# SD_Sniffer.net
KiCad netlist of a schematic drawn in EAGLE
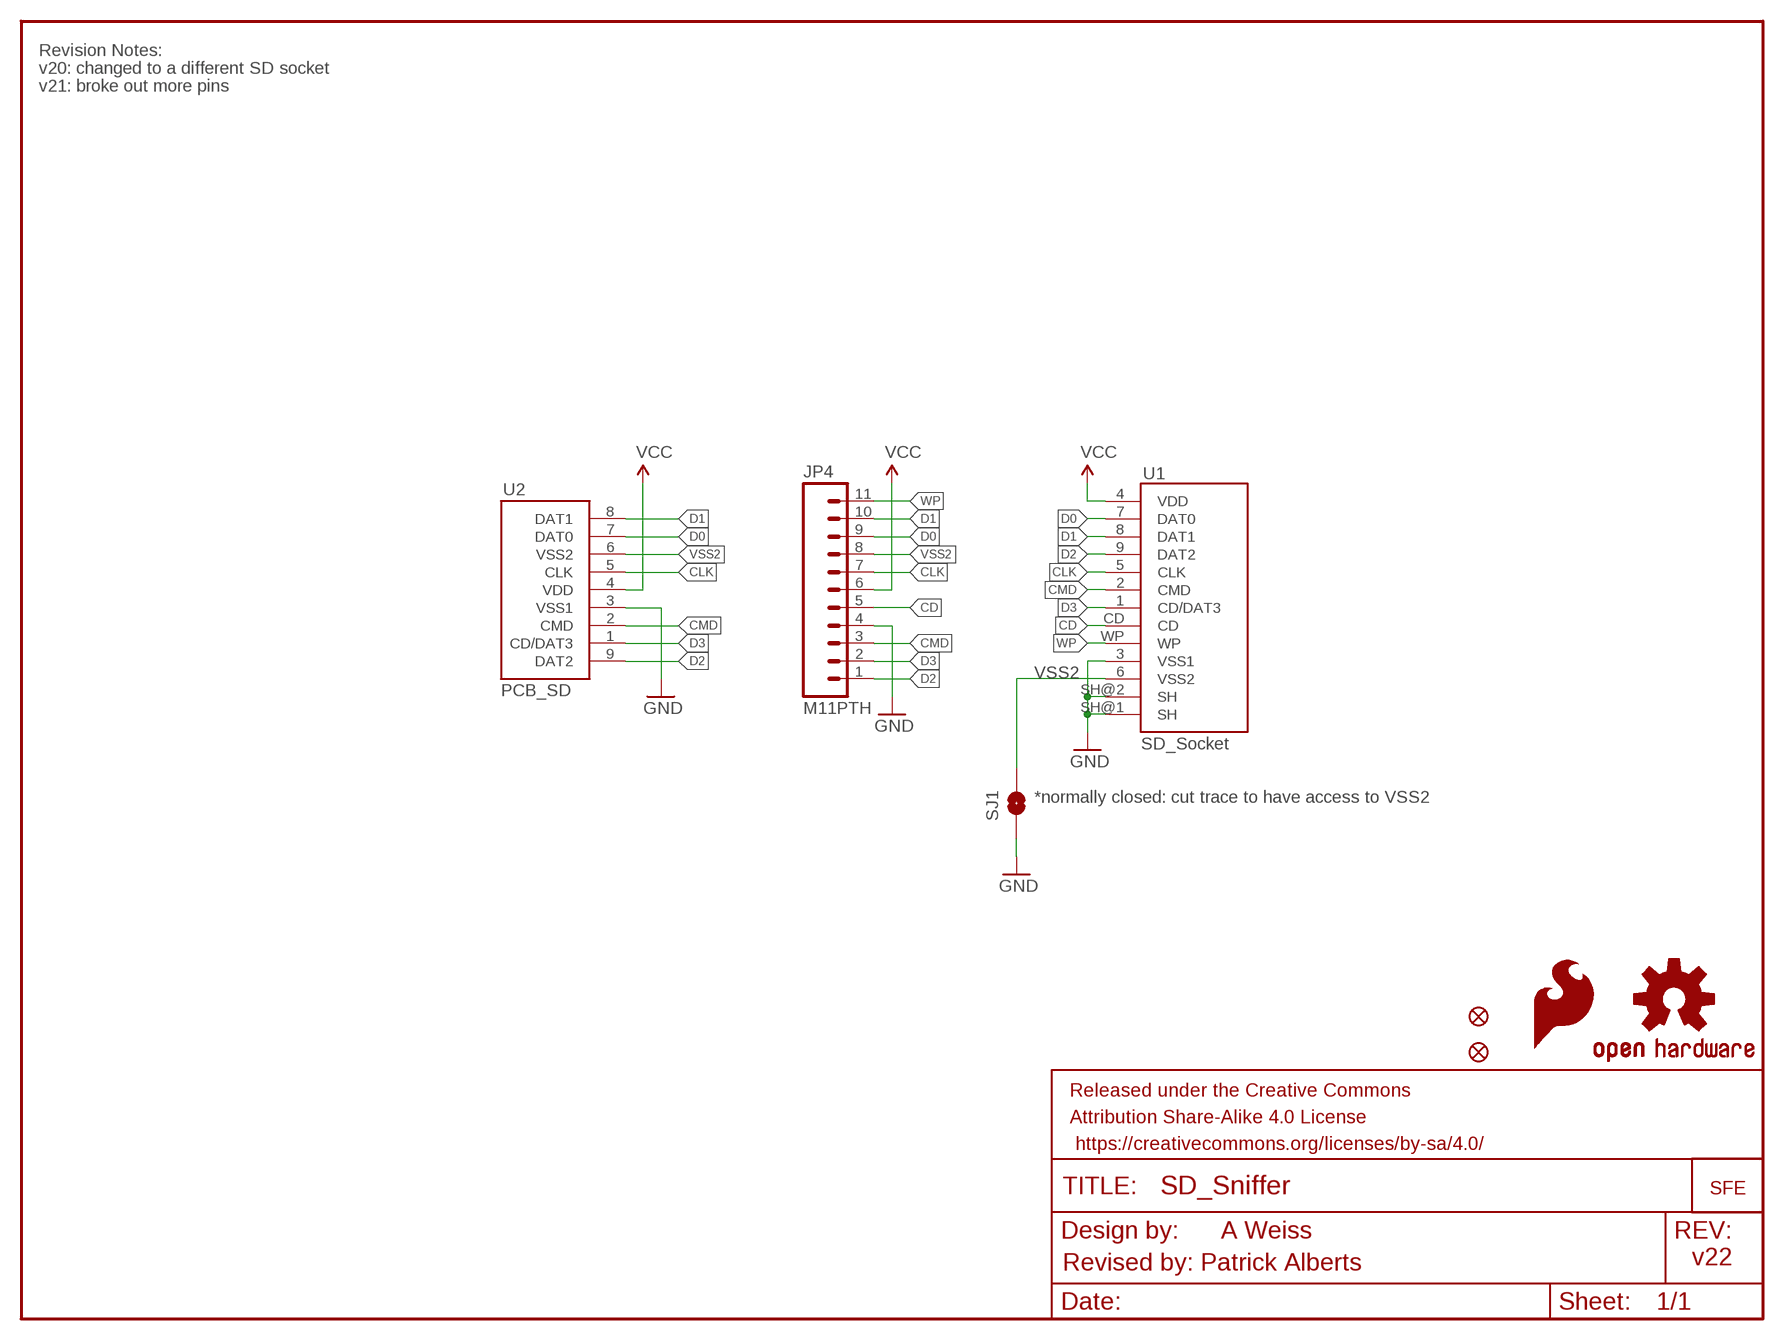
[diagram p0: schematic, sheet 1]

(export (version "E")
  (design (tool "Eeschema 10.0.6"))
  (components
    (comp (ref "FRAME1")
      (value "FRAME-LETTER")
      (footprint "eagle-import:CREATIVE_COMMONS")
      (libsource (lib "eagle-import") (part "FRAME-LETTER"))
    )
    (comp (ref "JP2")
      (value "FIDUCIALUFIDUCIAL")
      (footprint "eagle-import:MICRO-FIDUCIAL")
      (libsource (lib "eagle-import") (part "FIDUCIALUFIDUCIAL"))
    )
    (comp (ref "JP3")
      (value "FIDUCIALUFIDUCIAL")
      (footprint "eagle-import:MICRO-FIDUCIAL")
      (libsource (lib "eagle-import") (part "FIDUCIALUFIDUCIAL"))
    )
    (comp (ref "JP4")
      (value "M11PTH")
      (footprint "eagle-import:1X11")
      (libsource (lib "eagle-import") (part "M11PTH"))
    )
    (comp (ref "LOGO")
      (value "LOGO-SFENEW")
      (footprint "eagle-import:SFE-NEW-WEBLOGO")
      (libsource (lib "eagle-import") (part "LOGO-SFENEW"))
    )
    (comp (ref "SJ1")
      (value "SOLDERJUMPERTRACE")
      (footprint "eagle-import:SJ_2S-TRACE")
      (libsource (lib "eagle-import") (part "SOLDERJUMPERTRACE"))
    )
    (comp (ref "U$2")
      (value "OSHW-LOGOS")
      (footprint "eagle-import:OSHW-LOGO-S")
      (libsource (lib "eagle-import") (part "OSHW-LOGOS"))
    )
    (comp (ref "U$4")
      (value "SFE_LOGO_FLAME.2_INCH")
      (footprint "eagle-import:SFE_LOGO_FLAME_.2")
      (libsource (lib "eagle-import") (part "SFE_LOGO_FLAME.2_INCH"))
    )
    (comp (ref "U1")
      (value "SD_CARD_SOCKET")
      (footprint "eagle-import:SD_1_1")
      (libsource (lib "eagle-import") (part "SD_CARD_SOCKET"))
    )
    (comp (ref "U2")
      (value "SD_MMC_CARDSD_PCB")
      (footprint "eagle-import:SD-MMC-CARD")
      (libsource (lib "eagle-import") (part "SD_MMC_CARDSD_PCB"))
    )
  )
  (nets
    (net (code "1") (name "CD") (class "Default")
      (node (ref "JP4") (pin "5") (pinfunction "5_5") (pintype "passive"))
      (node (ref "U1") (pin "CD") (pinfunction "CD_CD") (pintype "bidirectional"))
    )
    (net (code "2") (name "CLK") (class "Default")
      (node (ref "JP4") (pin "7") (pinfunction "7_7") (pintype "passive"))
      (node (ref "U1") (pin "5") (pinfunction "CLK_5") (pintype "bidirectional"))
      (node (ref "U2") (pin "5") (pinfunction "CLK_5") (pintype "bidirectional"))
    )
    (net (code "3") (name "CMD") (class "Default")
      (node (ref "JP4") (pin "3") (pinfunction "3_3") (pintype "passive"))
      (node (ref "U1") (pin "2") (pinfunction "CMD_2") (pintype "bidirectional"))
      (node (ref "U2") (pin "2") (pinfunction "CMD_2") (pintype "bidirectional"))
    )
    (net (code "4") (name "D0") (class "Default")
      (node (ref "JP4") (pin "9") (pinfunction "9_9") (pintype "passive"))
      (node (ref "U1") (pin "7") (pinfunction "DAT0_7") (pintype "bidirectional"))
      (node (ref "U2") (pin "7") (pinfunction "DAT0_7") (pintype "bidirectional"))
    )
    (net (code "5") (name "D1") (class "Default")
      (node (ref "JP4") (pin "10") (pinfunction "10_10") (pintype "passive"))
      (node (ref "U1") (pin "8") (pinfunction "DAT1_8") (pintype "bidirectional"))
      (node (ref "U2") (pin "8") (pinfunction "DAT1_8") (pintype "bidirectional"))
    )
    (net (code "6") (name "D2") (class "Default")
      (node (ref "JP4") (pin "1") (pinfunction "1_1") (pintype "passive"))
      (node (ref "U1") (pin "9") (pinfunction "DAT2_9") (pintype "bidirectional"))
      (node (ref "U2") (pin "9") (pinfunction "DAT2_9") (pintype "bidirectional"))
    )
    (net (code "7") (name "D3") (class "Default")
      (node (ref "JP4") (pin "2") (pinfunction "2_2") (pintype "passive"))
      (node (ref "U1") (pin "1") (pinfunction "CD/DAT3_1") (pintype "bidirectional"))
      (node (ref "U2") (pin "1") (pinfunction "CD/DAT3_1") (pintype "bidirectional"))
    )
    (net (code "8") (name "GND") (class "Default")
      (node (ref "JP4") (pin "4") (pinfunction "4_4") (pintype "passive"))
      (node (ref "SJ1") (pin "1") (pinfunction "1_1") (pintype "passive"))
      (node (ref "U1") (pin "3") (pinfunction "VSS1_3") (pintype "power_in"))
      (node (ref "U1") (pin "SH@1") (pinfunction "SH_SH@1") (pintype "bidirectional"))
      (node (ref "U1") (pin "SH@2") (pinfunction "SH_SH@2") (pintype "bidirectional"))
      (node (ref "U2") (pin "3") (pinfunction "VSS1_3") (pintype "bidirectional"))
    )
    (net (code "9") (name "VCC") (class "Default")
      (node (ref "JP4") (pin "6") (pinfunction "6_6") (pintype "passive"))
      (node (ref "U1") (pin "4") (pinfunction "VDD_4") (pintype "power_in"))
      (node (ref "U2") (pin "4") (pinfunction "VDD_4") (pintype "bidirectional"))
    )
    (net (code "10") (name "VSS2") (class "Default")
      (node (ref "JP4") (pin "8") (pinfunction "8_8") (pintype "passive"))
      (node (ref "SJ1") (pin "2") (pinfunction "2_2") (pintype "passive"))
      (node (ref "U1") (pin "6") (pinfunction "VSS2_6") (pintype "power_in"))
      (node (ref "U2") (pin "6") (pinfunction "VSS2_6") (pintype "bidirectional"))
    )
    (net (code "11") (name "WP") (class "Default")
      (node (ref "JP4") (pin "11") (pinfunction "11_11") (pintype "passive"))
      (node (ref "U1") (pin "WP") (pinfunction "WP_WP") (pintype "bidirectional"))
    )
  )
)
